# Circuit_Complet.net
KiCad netlist of a schematic drawn in Altium Designer
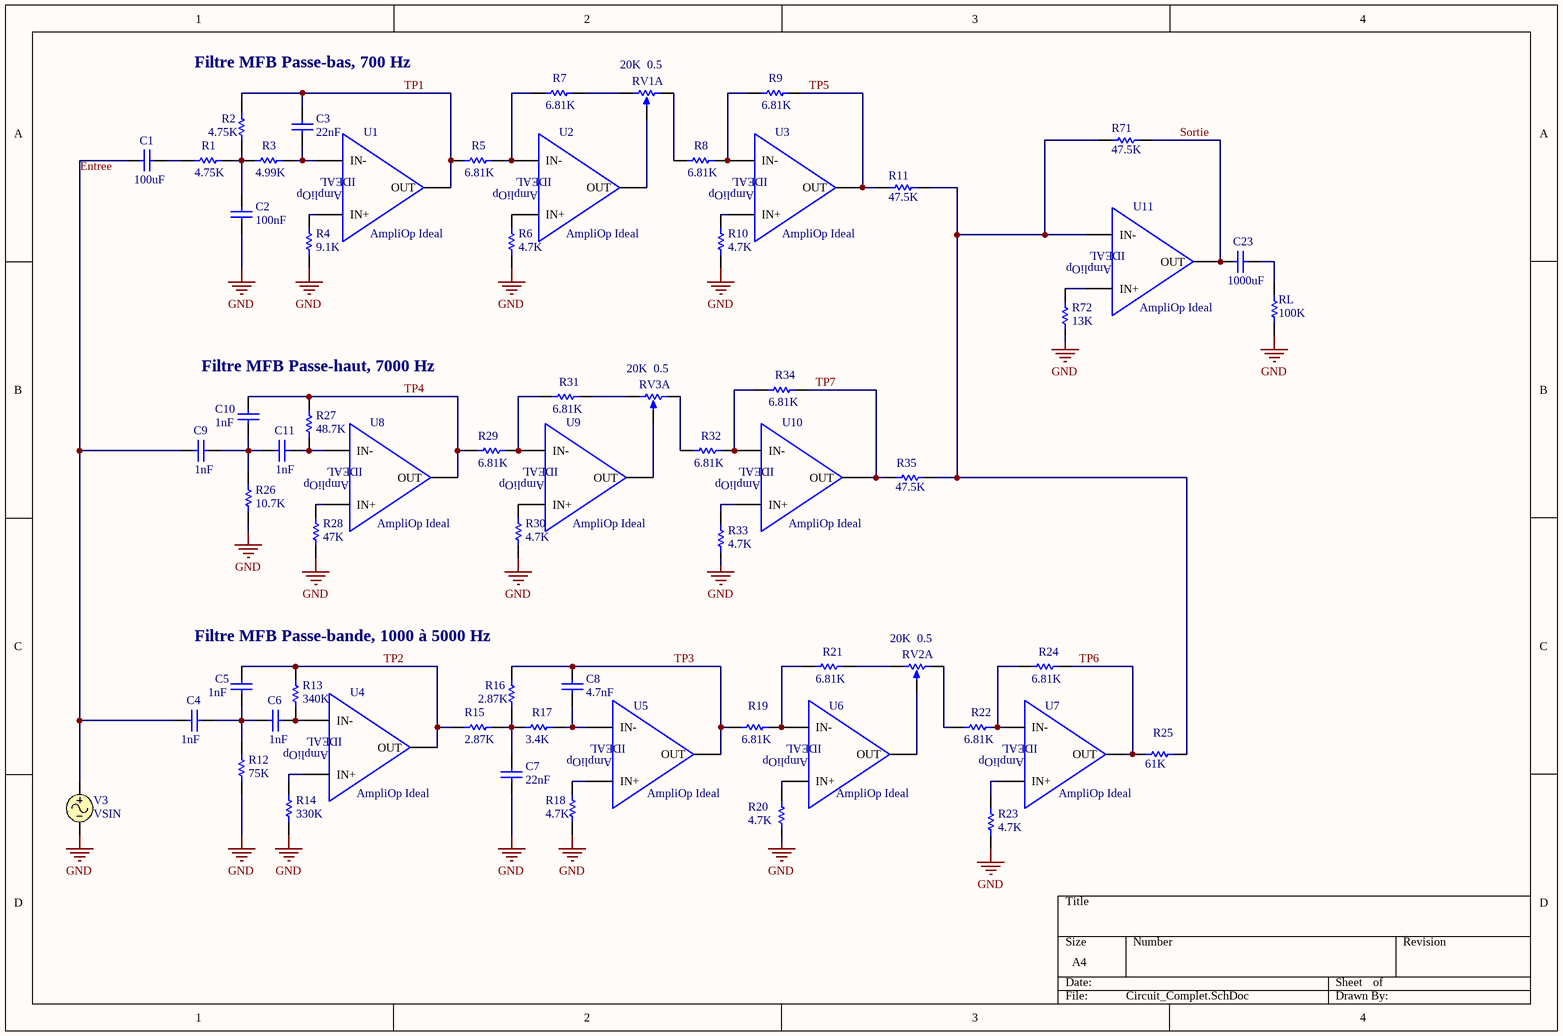
[diagram p0: Circuit_Complet.SchDoc]

(export (version "E")
  (design (tool "Eeschema 10.0.6"))
  (components
    (comp (ref "C1")
      (value "100uF")
      (footprint "RAD-0.3")
      (description "Capacitor")
      (fields (field (name "Comment") "Cap") (field (name "PUBLISHER") "Altium Limited"))
      (libsource (lib "Miscellaneous Devices") (part "Cap"))
    )
    (comp (ref "C2")
      (value "100nF")
      (footprint "RAD-0.3")
      (description "Capacitor")
      (fields (field (name "Comment") "Cap") (field (name "PUBLISHER") "Altium Limited"))
      (libsource (lib "Miscellaneous Devices") (part "Cap"))
    )
    (comp (ref "C3")
      (value "22nF")
      (footprint "RAD-0.3")
      (description "Capacitor")
      (fields (field (name "Comment") "Cap") (field (name "PUBLISHER") "Altium Limited"))
      (libsource (lib "Miscellaneous Devices") (part "Cap"))
    )
    (comp (ref "C4")
      (value "1nF")
      (footprint "RAD-0.3")
      (description "Capacitor")
      (fields (field (name "Comment") "Cap") (field (name "PUBLISHER") "Altium Limited"))
      (libsource (lib "Miscellaneous Devices") (part "Cap"))
    )
    (comp (ref "C5")
      (value "1nF")
      (footprint "RAD-0.3")
      (description "Capacitor")
      (fields (field (name "Comment") "Cap") (field (name "PUBLISHER") "Altium Limited"))
      (libsource (lib "Miscellaneous Devices") (part "Cap"))
    )
    (comp (ref "C6")
      (value "1nF")
      (footprint "RAD-0.3")
      (description "Capacitor")
      (fields (field (name "Comment") "Cap") (field (name "PUBLISHER") "Altium Limited"))
      (libsource (lib "Miscellaneous Devices") (part "Cap"))
    )
    (comp (ref "C7")
      (value "22nF")
      (footprint "RAD-0.3")
      (description "Capacitor")
      (fields (field (name "Comment") "Cap") (field (name "PUBLISHER") "Altium Limited"))
      (libsource (lib "Miscellaneous Devices") (part "Cap"))
    )
    (comp (ref "C8")
      (value "4.7nF")
      (footprint "RAD-0.3")
      (description "Capacitor")
      (fields (field (name "Comment") "Cap") (field (name "PUBLISHER") "Altium Limited"))
      (libsource (lib "Miscellaneous Devices") (part "Cap"))
    )
    (comp (ref "C9")
      (value "1nF")
      (footprint "RAD-0.3")
      (description "Capacitor")
      (fields (field (name "Comment") "Cap") (field (name "PUBLISHER") "Altium Limited"))
      (libsource (lib "Miscellaneous Devices") (part "Cap"))
    )
    (comp (ref "C10")
      (value "1nF")
      (footprint "RAD-0.3")
      (description "Capacitor")
      (fields (field (name "Comment") "Cap") (field (name "PUBLISHER") "Altium Limited"))
      (libsource (lib "Miscellaneous Devices") (part "Cap"))
    )
    (comp (ref "C11")
      (value "1nF")
      (footprint "RAD-0.3")
      (description "Capacitor")
      (fields (field (name "Comment") "Cap") (field (name "PUBLISHER") "Altium Limited"))
      (libsource (lib "Miscellaneous Devices") (part "Cap"))
    )
    (comp (ref "C23")
      (value "1000uF")
      (footprint "RAD-0.3")
      (description "Capacitor")
      (fields (field (name "Comment") "Cap") (field (name "PUBLISHER") "Altium Limited"))
      (libsource (lib "Miscellaneous Devices") (part "Cap"))
    )
    (comp (ref "R1")
      (value "4.75K")
      (footprint "AXIAL-0.3")
      (description "Resistor")
      (fields (field (name "Comment") "Res1") (field (name "PUBLISHER") "Altium Limited"))
      (libsource (lib "Miscellaneous Devices") (part "Res1"))
    )
    (comp (ref "R2")
      (value "4.75K")
      (footprint "AXIAL-0.3")
      (description "Resistor")
      (fields (field (name "Comment") "Res1") (field (name "PUBLISHER") "Altium Limited"))
      (libsource (lib "Miscellaneous Devices") (part "Res1"))
    )
    (comp (ref "R3")
      (value "4.99K")
      (footprint "AXIAL-0.3")
      (description "Resistor")
      (fields (field (name "Comment") "Res1") (field (name "PUBLISHER") "Altium Limited"))
      (libsource (lib "Miscellaneous Devices") (part "Res1"))
    )
    (comp (ref "R4")
      (value "9.1K")
      (footprint "AXIAL-0.3")
      (description "Resistor")
      (fields (field (name "Comment") "Res1") (field (name "PUBLISHER") "Altium Limited"))
      (libsource (lib "Miscellaneous Devices") (part "Res1"))
    )
    (comp (ref "R5")
      (value "6.81K")
      (footprint "AXIAL-0.3")
      (description "Resistor")
      (fields (field (name "Comment") "Res1") (field (name "PUBLISHER") "Altium Limited"))
      (libsource (lib "Miscellaneous Devices") (part "Res1"))
    )
    (comp (ref "R6")
      (value "4.7K")
      (footprint "AXIAL-0.3")
      (description "Resistor")
      (fields (field (name "Comment") "Res1") (field (name "PUBLISHER") "Altium Limited"))
      (libsource (lib "Miscellaneous Devices") (part "Res1"))
    )
    (comp (ref "R7")
      (value "6.81K")
      (footprint "AXIAL-0.3")
      (description "Resistor")
      (fields (field (name "Comment") "Res1") (field (name "PUBLISHER") "Altium Limited"))
      (libsource (lib "Miscellaneous Devices") (part "Res1"))
    )
    (comp (ref "R8")
      (value "6.81K")
      (footprint "AXIAL-0.3")
      (description "Resistor")
      (fields (field (name "Comment") "Res1") (field (name "PUBLISHER") "Altium Limited"))
      (libsource (lib "Miscellaneous Devices") (part "Res1"))
    )
    (comp (ref "R9")
      (value "6.81K")
      (footprint "AXIAL-0.3")
      (description "Resistor")
      (fields (field (name "Comment") "Res1") (field (name "PUBLISHER") "Altium Limited"))
      (libsource (lib "Miscellaneous Devices") (part "Res1"))
    )
    (comp (ref "R10")
      (value "4.7K")
      (footprint "AXIAL-0.3")
      (description "Resistor")
      (fields (field (name "Comment") "Res1") (field (name "PUBLISHER") "Altium Limited"))
      (libsource (lib "Miscellaneous Devices") (part "Res1"))
    )
    (comp (ref "R11")
      (value "47.5K")
      (footprint "AXIAL-0.3")
      (description "Resistor")
      (fields (field (name "Comment") "Res1") (field (name "PUBLISHER") "Altium Limited"))
      (libsource (lib "Miscellaneous Devices") (part "Res1"))
    )
    (comp (ref "R12")
      (value "75K")
      (footprint "AXIAL-0.3")
      (description "Resistor")
      (fields (field (name "Comment") "Res1") (field (name "PUBLISHER") "Altium Limited"))
      (libsource (lib "Miscellaneous Devices") (part "Res1"))
    )
    (comp (ref "R13")
      (value "340K")
      (footprint "AXIAL-0.3")
      (description "Resistor")
      (fields (field (name "Comment") "Res1") (field (name "PUBLISHER") "Altium Limited"))
      (libsource (lib "Miscellaneous Devices") (part "Res1"))
    )
    (comp (ref "R14")
      (value "330K")
      (footprint "AXIAL-0.3")
      (description "Resistor")
      (fields (field (name "Comment") "Res1") (field (name "PUBLISHER") "Altium Limited"))
      (libsource (lib "Miscellaneous Devices") (part "Res1"))
    )
    (comp (ref "R15")
      (value "2.87K")
      (footprint "AXIAL-0.3")
      (description "Resistor")
      (fields (field (name "Comment") "Res1") (field (name "PUBLISHER") "Altium Limited"))
      (libsource (lib "Miscellaneous Devices") (part "Res1"))
    )
    (comp (ref "R16")
      (value "2.87K")
      (footprint "AXIAL-0.3")
      (description "Resistor")
      (fields (field (name "Comment") "Res1") (field (name "PUBLISHER") "Altium Limited"))
      (libsource (lib "Miscellaneous Devices") (part "Res1"))
    )
    (comp (ref "R17")
      (value "3.4K")
      (footprint "AXIAL-0.3")
      (description "Resistor")
      (fields (field (name "Comment") "Res1") (field (name "PUBLISHER") "Altium Limited"))
      (libsource (lib "Miscellaneous Devices") (part "Res1"))
    )
    (comp (ref "R18")
      (value "4.7K")
      (footprint "AXIAL-0.3")
      (description "Resistor")
      (fields (field (name "Comment") "Res1") (field (name "PUBLISHER") "Altium Limited"))
      (libsource (lib "Miscellaneous Devices") (part "Res1"))
    )
    (comp (ref "R19")
      (value "6.81K")
      (footprint "AXIAL-0.3")
      (description "Resistor")
      (fields (field (name "Comment") "Res1") (field (name "PUBLISHER") "Altium Limited"))
      (libsource (lib "Miscellaneous Devices") (part "Res1"))
    )
    (comp (ref "R20")
      (value "4.7K")
      (footprint "AXIAL-0.3")
      (description "Resistor")
      (fields (field (name "Comment") "Res1") (field (name "PUBLISHER") "Altium Limited"))
      (libsource (lib "Miscellaneous Devices") (part "Res1"))
    )
    (comp (ref "R21")
      (value "6.81K")
      (footprint "AXIAL-0.3")
      (description "Resistor")
      (fields (field (name "Comment") "Res1") (field (name "PUBLISHER") "Altium Limited"))
      (libsource (lib "Miscellaneous Devices") (part "Res1"))
    )
    (comp (ref "R22")
      (value "6.81K")
      (footprint "AXIAL-0.3")
      (description "Resistor")
      (fields (field (name "Comment") "Res1") (field (name "PUBLISHER") "Altium Limited"))
      (libsource (lib "Miscellaneous Devices") (part "Res1"))
    )
    (comp (ref "R23")
      (value "4.7K")
      (footprint "AXIAL-0.3")
      (description "Resistor")
      (fields (field (name "Comment") "Res1") (field (name "PUBLISHER") "Altium Limited"))
      (libsource (lib "Miscellaneous Devices") (part "Res1"))
    )
    (comp (ref "R24")
      (value "6.81K")
      (footprint "AXIAL-0.3")
      (description "Resistor")
      (fields (field (name "Comment") "Res1") (field (name "PUBLISHER") "Altium Limited"))
      (libsource (lib "Miscellaneous Devices") (part "Res1"))
    )
    (comp (ref "R25")
      (value "61K")
      (footprint "AXIAL-0.3")
      (description "Resistor")
      (fields (field (name "Comment") "Res1") (field (name "PUBLISHER") "Altium Limited"))
      (libsource (lib "Miscellaneous Devices") (part "Res1"))
    )
    (comp (ref "R26")
      (value "10.7K")
      (footprint "AXIAL-0.3")
      (description "Resistor")
      (fields (field (name "Comment") "Res1") (field (name "PUBLISHER") "Altium Limited"))
      (libsource (lib "Miscellaneous Devices") (part "Res1"))
    )
    (comp (ref "R27")
      (value "48.7K")
      (footprint "AXIAL-0.3")
      (description "Resistor")
      (fields (field (name "Comment") "Res1") (field (name "PUBLISHER") "Altium Limited"))
      (libsource (lib "Miscellaneous Devices") (part "Res1"))
    )
    (comp (ref "R28")
      (value "47K")
      (footprint "AXIAL-0.3")
      (description "Resistor")
      (fields (field (name "Comment") "Res1") (field (name "PUBLISHER") "Altium Limited"))
      (libsource (lib "Miscellaneous Devices") (part "Res1"))
    )
    (comp (ref "R29")
      (value "6.81K")
      (footprint "AXIAL-0.3")
      (description "Resistor")
      (fields (field (name "Comment") "Res1") (field (name "PUBLISHER") "Altium Limited"))
      (libsource (lib "Miscellaneous Devices") (part "Res1"))
    )
    (comp (ref "R30")
      (value "4.7K")
      (footprint "AXIAL-0.3")
      (description "Resistor")
      (fields (field (name "Comment") "Res1") (field (name "PUBLISHER") "Altium Limited"))
      (libsource (lib "Miscellaneous Devices") (part "Res1"))
    )
    (comp (ref "R31")
      (value "6.81K")
      (footprint "AXIAL-0.3")
      (description "Resistor")
      (fields (field (name "Comment") "Res1") (field (name "PUBLISHER") "Altium Limited"))
      (libsource (lib "Miscellaneous Devices") (part "Res1"))
    )
    (comp (ref "R32")
      (value "6.81K")
      (footprint "AXIAL-0.3")
      (description "Resistor")
      (fields (field (name "Comment") "Res1") (field (name "PUBLISHER") "Altium Limited"))
      (libsource (lib "Miscellaneous Devices") (part "Res1"))
    )
    (comp (ref "R33")
      (value "4.7K")
      (footprint "AXIAL-0.3")
      (description "Resistor")
      (fields (field (name "Comment") "Res1") (field (name "PUBLISHER") "Altium Limited"))
      (libsource (lib "Miscellaneous Devices") (part "Res1"))
    )
    (comp (ref "R34")
      (value "6.81K")
      (footprint "AXIAL-0.3")
      (description "Resistor")
      (fields (field (name "Comment") "Res1") (field (name "PUBLISHER") "Altium Limited"))
      (libsource (lib "Miscellaneous Devices") (part "Res1"))
    )
    (comp (ref "R35")
      (value "47.5K")
      (footprint "AXIAL-0.3")
      (description "Resistor")
      (fields (field (name "Comment") "Res1") (field (name "PUBLISHER") "Altium Limited"))
      (libsource (lib "Miscellaneous Devices") (part "Res1"))
    )
    (comp (ref "R71")
      (value "47.5K")
      (footprint "AXIAL-0.3")
      (description "Resistor")
      (fields (field (name "Comment") "Res1") (field (name "PUBLISHER") "Altium Limited"))
      (libsource (lib "Miscellaneous Devices") (part "Res1"))
    )
    (comp (ref "R72")
      (value "13K")
      (footprint "AXIAL-0.3")
      (description "Resistor")
      (fields (field (name "Comment") "Res1") (field (name "PUBLISHER") "Altium Limited"))
      (libsource (lib "Miscellaneous Devices") (part "Res1"))
    )
    (comp (ref "RL")
      (value "100K")
      (footprint "AXIAL-0.3")
      (description "Resistor")
      (fields (field (name "Comment") "Res1") (field (name "PUBLISHER") "Altium Limited"))
      (libsource (lib "Miscellaneous Devices") (part "Res1"))
    )
    (comp (ref "RV1A")
      (value "20K")
      (footprint "VR5")
      (description "Potentiometer")
      (fields
        (field (name "SET POSITION") "0.5")
        (field (name "Comment") "RPot")
        (field (name "PUBLISHER") "Altium Limited")
      )
      (libsource (lib "Miscellaneous Devices") (part "RPot"))
    )
    (comp (ref "RV2A")
      (value "20K")
      (footprint "VR5")
      (description "Potentiometer")
      (fields
        (field (name "SET POSITION") "0.5")
        (field (name "Comment") "RPot")
        (field (name "PUBLISHER") "Altium Limited")
      )
      (libsource (lib "Miscellaneous Devices") (part "RPot"))
    )
    (comp (ref "RV3A")
      (value "20K")
      (footprint "VR5")
      (description "Potentiometer")
      (fields
        (field (name "SET POSITION") "0.5")
        (field (name "Comment") "RPot")
        (field (name "PUBLISHER") "Altium Limited")
      )
      (libsource (lib "Miscellaneous Devices") (part "RPot"))
    )
    (comp (ref "U1") (value "AmpliOp Ideal") (libsource (lib "Librarie_S2") (part "AmpliOp_ideal")))
    (comp (ref "U2") (value "AmpliOp Ideal") (libsource (lib "Librarie_S2") (part "AmpliOp_ideal")))
    (comp (ref "U3") (value "AmpliOp Ideal") (libsource (lib "Librarie_S2") (part "AmpliOp_ideal")))
    (comp (ref "U4") (value "AmpliOp Ideal") (libsource (lib "Librarie_S2") (part "AmpliOp_ideal")))
    (comp (ref "U5") (value "AmpliOp Ideal") (libsource (lib "Librarie_S2") (part "AmpliOp_ideal")))
    (comp (ref "U6") (value "AmpliOp Ideal") (libsource (lib "Librarie_S2") (part "AmpliOp_ideal")))
    (comp (ref "U7") (value "AmpliOp Ideal") (libsource (lib "Librarie_S2") (part "AmpliOp_ideal")))
    (comp (ref "U8") (value "AmpliOp Ideal") (libsource (lib "Librarie_S2") (part "AmpliOp_ideal")))
    (comp (ref "U9") (value "AmpliOp Ideal") (libsource (lib "Librarie_S2") (part "AmpliOp_ideal")))
    (comp (ref "U10") (value "AmpliOp Ideal") (libsource (lib "Librarie_S2") (part "AmpliOp_ideal")))
    (comp (ref "U11") (value "AmpliOp Ideal") (libsource (lib "Librarie_S2") (part "AmpliOp_ideal")))
    (comp (ref "V3")
      (value "VSIN")
      (description "Sinusoidal Voltage Source")
      (fields (field (name "PUBLISHER") "Altium Limited"))
      (libsource (lib "Simulation Sources") (part "VSIN"))
    )
  )
  (nets
    (net (code "1") (name "/Entree") (class "Default")
      (node (ref "C1") (pin "1") (pinfunction "1_1") (pintype "passive"))
      (node (ref "C4") (pin "1") (pinfunction "1_1") (pintype "passive"))
      (node (ref "C9") (pin "1") (pinfunction "1_1") (pintype "passive"))
      (node (ref "V3") (pin "1") (pinfunction "1_1") (pintype "passive"))
    )
    (net (code "2") (name "/Sortie") (class "Default")
      (node (ref "C23") (pin "1") (pinfunction "1_1") (pintype "passive"))
      (node (ref "R71") (pin "2") (pinfunction "2_2") (pintype "passive"))
      (node (ref "U11") (pin "3") (pinfunction "OUT_3") (pintype "passive"))
    )
    (net (code "3") (name "/TP1") (class "Default")
      (node (ref "C3") (pin "1") (pinfunction "1_1") (pintype "passive"))
      (node (ref "R2") (pin "1") (pinfunction "1_1") (pintype "passive"))
      (node (ref "R5") (pin "1") (pinfunction "1_1") (pintype "passive"))
      (node (ref "U1") (pin "3") (pinfunction "OUT_3") (pintype "passive"))
    )
    (net (code "4") (name "/TP2") (class "Default")
      (node (ref "C5") (pin "1") (pinfunction "1_1") (pintype "passive"))
      (node (ref "R13") (pin "1") (pinfunction "1_1") (pintype "passive"))
      (node (ref "R15") (pin "1") (pinfunction "1_1") (pintype "passive"))
      (node (ref "U4") (pin "3") (pinfunction "OUT_3") (pintype "passive"))
    )
    (net (code "5") (name "/TP3") (class "Default")
      (node (ref "C8") (pin "1") (pinfunction "1_1") (pintype "passive"))
      (node (ref "R16") (pin "1") (pinfunction "1_1") (pintype "passive"))
      (node (ref "R19") (pin "1") (pinfunction "1_1") (pintype "passive"))
      (node (ref "U5") (pin "3") (pinfunction "OUT_3") (pintype "passive"))
    )
    (net (code "6") (name "/TP4") (class "Default")
      (node (ref "C10") (pin "1") (pinfunction "1_1") (pintype "passive"))
      (node (ref "R27") (pin "1") (pinfunction "1_1") (pintype "passive"))
      (node (ref "R29") (pin "1") (pinfunction "1_1") (pintype "passive"))
      (node (ref "U8") (pin "3") (pinfunction "OUT_3") (pintype "passive"))
    )
    (net (code "7") (name "/TP5") (class "Default")
      (node (ref "R11") (pin "1") (pinfunction "1_1") (pintype "passive"))
      (node (ref "R9") (pin "2") (pinfunction "2_2") (pintype "passive"))
      (node (ref "U3") (pin "3") (pinfunction "OUT_3") (pintype "passive"))
    )
    (net (code "8") (name "/TP6") (class "Default")
      (node (ref "R24") (pin "2") (pinfunction "2_2") (pintype "passive"))
      (node (ref "R25") (pin "1") (pinfunction "1_1") (pintype "passive"))
      (node (ref "U7") (pin "3") (pinfunction "OUT_3") (pintype "passive"))
    )
    (net (code "9") (name "/TP7") (class "Default")
      (node (ref "R34") (pin "2") (pinfunction "2_2") (pintype "passive"))
      (node (ref "R35") (pin "1") (pinfunction "1_1") (pintype "passive"))
      (node (ref "U10") (pin "3") (pinfunction "OUT_3") (pintype "passive"))
    )
    (net (code "10") (name "GND") (class "Default")
      (node (ref "C2") (pin "2") (pinfunction "2_2") (pintype "passive"))
      (node (ref "C7") (pin "2") (pinfunction "2_2") (pintype "passive"))
      (node (ref "R10") (pin "2") (pinfunction "2_2") (pintype "passive"))
      (node (ref "R12") (pin "2") (pinfunction "2_2") (pintype "passive"))
      (node (ref "R14") (pin "2") (pinfunction "2_2") (pintype "passive"))
      (node (ref "R18") (pin "2") (pinfunction "2_2") (pintype "passive"))
      (node (ref "R20") (pin "2") (pinfunction "2_2") (pintype "passive"))
      (node (ref "R23") (pin "2") (pinfunction "2_2") (pintype "passive"))
      (node (ref "R26") (pin "2") (pinfunction "2_2") (pintype "passive"))
      (node (ref "R28") (pin "2") (pinfunction "2_2") (pintype "passive"))
      (node (ref "R30") (pin "2") (pinfunction "2_2") (pintype "passive"))
      (node (ref "R33") (pin "2") (pinfunction "2_2") (pintype "passive"))
      (node (ref "R4") (pin "2") (pinfunction "2_2") (pintype "passive"))
      (node (ref "R6") (pin "2") (pinfunction "2_2") (pintype "passive"))
      (node (ref "R72") (pin "2") (pinfunction "2_2") (pintype "passive"))
      (node (ref "RL") (pin "1") (pinfunction "1_1") (pintype "passive"))
      (node (ref "V3") (pin "2") (pinfunction "2_2") (pintype "passive"))
    )
    (net (code "11") (name "Net-(C1-Pad2)") (class "Default")
      (node (ref "C1") (pin "2") (pinfunction "2_2") (pintype "passive"))
      (node (ref "R1") (pin "1") (pinfunction "1_1") (pintype "passive"))
    )
    (net (code "12") (name "Net-(C2-Pad1)") (class "Default")
      (node (ref "C2") (pin "1") (pinfunction "1_1") (pintype "passive"))
      (node (ref "R1") (pin "2") (pinfunction "2_2") (pintype "passive"))
      (node (ref "R2") (pin "2") (pinfunction "2_2") (pintype "passive"))
      (node (ref "R3") (pin "1") (pinfunction "1_1") (pintype "passive"))
    )
    (net (code "13") (name "Net-(C4-Pad2)") (class "Default")
      (node (ref "C4") (pin "2") (pinfunction "2_2") (pintype "passive"))
      (node (ref "C5") (pin "2") (pinfunction "2_2") (pintype "passive"))
      (node (ref "C6") (pin "1") (pinfunction "1_1") (pintype "passive"))
      (node (ref "R12") (pin "1") (pinfunction "1_1") (pintype "passive"))
    )
    (net (code "14") (name "Net-(C7-Pad1)") (class "Default")
      (node (ref "C7") (pin "1") (pinfunction "1_1") (pintype "passive"))
      (node (ref "R15") (pin "2") (pinfunction "2_2") (pintype "passive"))
      (node (ref "R16") (pin "2") (pinfunction "2_2") (pintype "passive"))
      (node (ref "R17") (pin "1") (pinfunction "1_1") (pintype "passive"))
    )
    (net (code "15") (name "Net-(C10-Pad2)") (class "Default")
      (node (ref "C10") (pin "2") (pinfunction "2_2") (pintype "passive"))
      (node (ref "C11") (pin "1") (pinfunction "1_1") (pintype "passive"))
      (node (ref "C9") (pin "2") (pinfunction "2_2") (pintype "passive"))
      (node (ref "R26") (pin "1") (pinfunction "1_1") (pintype "passive"))
    )
    (net (code "16") (name "Net-(C23-Pad2)") (class "Default")
      (node (ref "C23") (pin "2") (pinfunction "2_2") (pintype "passive"))
      (node (ref "RL") (pin "2") (pinfunction "2_2") (pintype "passive"))
    )
    (net (code "17") (name "Net-(RV1A-BOT)") (class "Default")
      (node (ref "R8") (pin "1") (pinfunction "1_1") (pintype "passive"))
      (node (ref "RV1A") (pin "2") (pinfunction "BOT_2") (pintype "passive"))
    )
    (net (code "18") (name "Net-(RV1A-TAP)") (class "Default")
      (node (ref "RV1A") (pin "3") (pinfunction "TAP_3") (pintype "passive"))
      (node (ref "U2") (pin "3") (pinfunction "OUT_3") (pintype "passive"))
    )
    (net (code "19") (name "Net-(RV1A-TOP)") (class "Default")
      (node (ref "R7") (pin "2") (pinfunction "2_2") (pintype "passive"))
      (node (ref "RV1A") (pin "1") (pinfunction "TOP_1") (pintype "passive"))
    )
    (net (code "20") (name "Net-(RV2A-BOT)") (class "Default")
      (node (ref "R22") (pin "1") (pinfunction "1_1") (pintype "passive"))
      (node (ref "RV2A") (pin "2") (pinfunction "BOT_2") (pintype "passive"))
    )
    (net (code "21") (name "Net-(RV2A-TAP)") (class "Default")
      (node (ref "RV2A") (pin "3") (pinfunction "TAP_3") (pintype "passive"))
      (node (ref "U6") (pin "3") (pinfunction "OUT_3") (pintype "passive"))
    )
    (net (code "22") (name "Net-(RV2A-TOP)") (class "Default")
      (node (ref "R21") (pin "2") (pinfunction "2_2") (pintype "passive"))
      (node (ref "RV2A") (pin "1") (pinfunction "TOP_1") (pintype "passive"))
    )
    (net (code "23") (name "Net-(RV3A-BOT)") (class "Default")
      (node (ref "R32") (pin "1") (pinfunction "1_1") (pintype "passive"))
      (node (ref "RV3A") (pin "2") (pinfunction "BOT_2") (pintype "passive"))
    )
    (net (code "24") (name "Net-(RV3A-TAP)") (class "Default")
      (node (ref "RV3A") (pin "3") (pinfunction "TAP_3") (pintype "passive"))
      (node (ref "U9") (pin "3") (pinfunction "OUT_3") (pintype "passive"))
    )
    (net (code "25") (name "Net-(RV3A-TOP)") (class "Default")
      (node (ref "R31") (pin "2") (pinfunction "2_2") (pintype "passive"))
      (node (ref "RV3A") (pin "1") (pinfunction "TOP_1") (pintype "passive"))
    )
    (net (code "26") (name "Net-(U1-IN+)") (class "Default")
      (node (ref "R4") (pin "1") (pinfunction "1_1") (pintype "passive"))
      (node (ref "U1") (pin "1") (pinfunction "IN+_1") (pintype "passive"))
    )
    (net (code "27") (name "Net-(U1-IN-)") (class "Default")
      (node (ref "C3") (pin "2") (pinfunction "2_2") (pintype "passive"))
      (node (ref "R3") (pin "2") (pinfunction "2_2") (pintype "passive"))
      (node (ref "U1") (pin "2") (pinfunction "IN-_2") (pintype "passive"))
    )
    (net (code "28") (name "Net-(U2-IN+)") (class "Default")
      (node (ref "R6") (pin "1") (pinfunction "1_1") (pintype "passive"))
      (node (ref "U2") (pin "1") (pinfunction "IN+_1") (pintype "passive"))
    )
    (net (code "29") (name "Net-(U2-IN-)") (class "Default")
      (node (ref "R5") (pin "2") (pinfunction "2_2") (pintype "passive"))
      (node (ref "R7") (pin "1") (pinfunction "1_1") (pintype "passive"))
      (node (ref "U2") (pin "2") (pinfunction "IN-_2") (pintype "passive"))
    )
    (net (code "30") (name "Net-(U3-IN+)") (class "Default")
      (node (ref "R10") (pin "1") (pinfunction "1_1") (pintype "passive"))
      (node (ref "U3") (pin "1") (pinfunction "IN+_1") (pintype "passive"))
    )
    (net (code "31") (name "Net-(U3-IN-)") (class "Default")
      (node (ref "R8") (pin "2") (pinfunction "2_2") (pintype "passive"))
      (node (ref "R9") (pin "1") (pinfunction "1_1") (pintype "passive"))
      (node (ref "U3") (pin "2") (pinfunction "IN-_2") (pintype "passive"))
    )
    (net (code "32") (name "Net-(U4-IN+)") (class "Default")
      (node (ref "R14") (pin "1") (pinfunction "1_1") (pintype "passive"))
      (node (ref "U4") (pin "1") (pinfunction "IN+_1") (pintype "passive"))
    )
    (net (code "33") (name "Net-(U4-IN-)") (class "Default")
      (node (ref "C6") (pin "2") (pinfunction "2_2") (pintype "passive"))
      (node (ref "R13") (pin "2") (pinfunction "2_2") (pintype "passive"))
      (node (ref "U4") (pin "2") (pinfunction "IN-_2") (pintype "passive"))
    )
    (net (code "34") (name "Net-(U5-IN+)") (class "Default")
      (node (ref "R18") (pin "1") (pinfunction "1_1") (pintype "passive"))
      (node (ref "U5") (pin "1") (pinfunction "IN+_1") (pintype "passive"))
    )
    (net (code "35") (name "Net-(U5-IN-)") (class "Default")
      (node (ref "C8") (pin "2") (pinfunction "2_2") (pintype "passive"))
      (node (ref "R17") (pin "2") (pinfunction "2_2") (pintype "passive"))
      (node (ref "U5") (pin "2") (pinfunction "IN-_2") (pintype "passive"))
    )
    (net (code "36") (name "Net-(U6-IN+)") (class "Default")
      (node (ref "R20") (pin "1") (pinfunction "1_1") (pintype "passive"))
      (node (ref "U6") (pin "1") (pinfunction "IN+_1") (pintype "passive"))
    )
    (net (code "37") (name "Net-(U6-IN-)") (class "Default")
      (node (ref "R19") (pin "2") (pinfunction "2_2") (pintype "passive"))
      (node (ref "R21") (pin "1") (pinfunction "1_1") (pintype "passive"))
      (node (ref "U6") (pin "2") (pinfunction "IN-_2") (pintype "passive"))
    )
    (net (code "38") (name "Net-(U7-IN+)") (class "Default")
      (node (ref "R23") (pin "1") (pinfunction "1_1") (pintype "passive"))
      (node (ref "U7") (pin "1") (pinfunction "IN+_1") (pintype "passive"))
    )
    (net (code "39") (name "Net-(U7-IN-)") (class "Default")
      (node (ref "R22") (pin "2") (pinfunction "2_2") (pintype "passive"))
      (node (ref "R24") (pin "1") (pinfunction "1_1") (pintype "passive"))
      (node (ref "U7") (pin "2") (pinfunction "IN-_2") (pintype "passive"))
    )
    (net (code "40") (name "Net-(U8-IN+)") (class "Default")
      (node (ref "R28") (pin "1") (pinfunction "1_1") (pintype "passive"))
      (node (ref "U8") (pin "1") (pinfunction "IN+_1") (pintype "passive"))
    )
    (net (code "41") (name "Net-(U8-IN-)") (class "Default")
      (node (ref "C11") (pin "2") (pinfunction "2_2") (pintype "passive"))
      (node (ref "R27") (pin "2") (pinfunction "2_2") (pintype "passive"))
      (node (ref "U8") (pin "2") (pinfunction "IN-_2") (pintype "passive"))
    )
    (net (code "42") (name "Net-(U9-IN+)") (class "Default")
      (node (ref "R30") (pin "1") (pinfunction "1_1") (pintype "passive"))
      (node (ref "U9") (pin "1") (pinfunction "IN+_1") (pintype "passive"))
    )
    (net (code "43") (name "Net-(U9-IN-)") (class "Default")
      (node (ref "R29") (pin "2") (pinfunction "2_2") (pintype "passive"))
      (node (ref "R31") (pin "1") (pinfunction "1_1") (pintype "passive"))
      (node (ref "U9") (pin "2") (pinfunction "IN-_2") (pintype "passive"))
    )
    (net (code "44") (name "Net-(U10-IN+)") (class "Default")
      (node (ref "R33") (pin "1") (pinfunction "1_1") (pintype "passive"))
      (node (ref "U10") (pin "1") (pinfunction "IN+_1") (pintype "passive"))
    )
    (net (code "45") (name "Net-(U10-IN-)") (class "Default")
      (node (ref "R32") (pin "2") (pinfunction "2_2") (pintype "passive"))
      (node (ref "R34") (pin "1") (pinfunction "1_1") (pintype "passive"))
      (node (ref "U10") (pin "2") (pinfunction "IN-_2") (pintype "passive"))
    )
    (net (code "46") (name "Net-(U11-IN+)") (class "Default")
      (node (ref "R72") (pin "1") (pinfunction "1_1") (pintype "passive"))
      (node (ref "U11") (pin "1") (pinfunction "IN+_1") (pintype "passive"))
    )
    (net (code "47") (name "Net-(U11-IN-)") (class "Default")
      (node (ref "R11") (pin "2") (pinfunction "2_2") (pintype "passive"))
      (node (ref "R25") (pin "2") (pinfunction "2_2") (pintype "passive"))
      (node (ref "R35") (pin "2") (pinfunction "2_2") (pintype "passive"))
      (node (ref "R71") (pin "1") (pinfunction "1_1") (pintype "passive"))
      (node (ref "U11") (pin "2") (pinfunction "IN-_2") (pintype "passive"))
    )
  )
)
